# Output_Schematic.net
KiCad netlist of a schematic drawn in Altium Designer
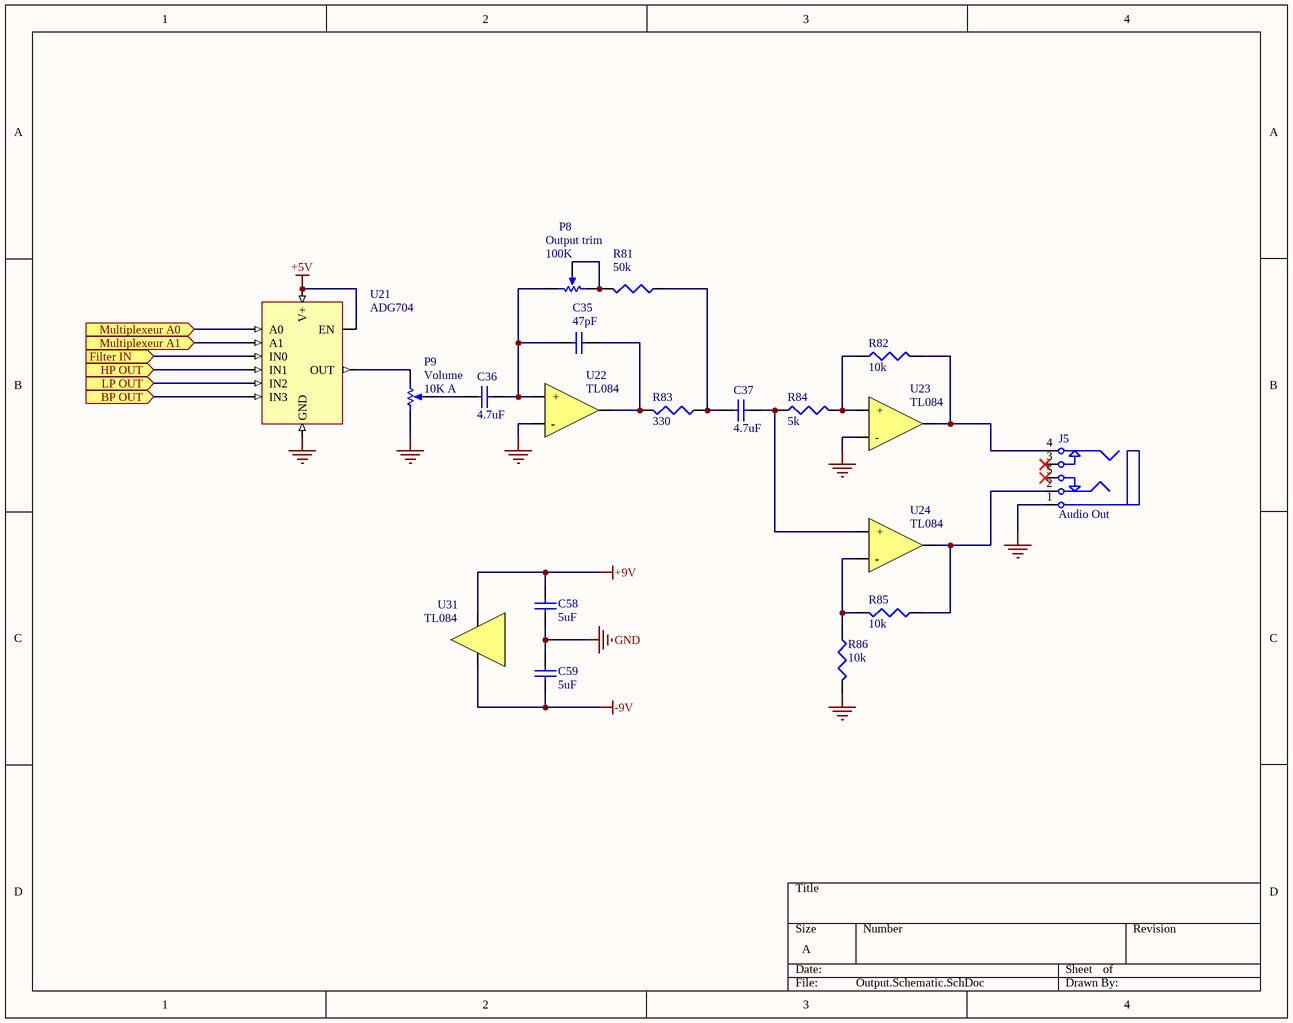
[diagram p0: Output.Schematic.SchDoc]

(export (version "E")
  (design (tool "Eeschema 10.0.6"))
  (components
    (comp (ref "C35")
      (value "47pF")
      (footprint "CAPC1608N")
      (description "Capacitor (Semiconductor SIM Model)")
      (fields (field (name "PUBLISHER") "Altium Limited"))
      (libsource (lib "Miscellaneous Devices") (part "Cap Semi"))
    )
    (comp (ref "C36")
      (value "4.7uF")
      (footprint "CAPC1608N")
      (description "Capacitor (Semiconductor SIM Model)")
      (fields (field (name "PUBLISHER") "Altium Limited"))
      (libsource (lib "Miscellaneous Devices") (part "Cap Semi"))
    )
    (comp (ref "C37")
      (value "4.7uF")
      (footprint "CAPC1608N")
      (description "Capacitor (Semiconductor SIM Model)")
      (fields (field (name "PUBLISHER") "Altium Limited"))
      (libsource (lib "Miscellaneous Devices") (part "Cap Semi"))
    )
    (comp (ref "C58")
      (value "5uF")
      (footprint "CAPC1608N")
      (description "Capacitor (Semiconductor SIM Model)")
      (fields (field (name "PUBLISHER") "Altium Limited"))
      (libsource (lib "Miscellaneous Devices") (part "Cap Semi"))
    )
    (comp (ref "C59")
      (value "5uF")
      (footprint "CAPC1608N")
      (description "Capacitor (Semiconductor SIM Model)")
      (fields (field (name "PUBLISHER") "Altium Limited"))
      (libsource (lib "Miscellaneous Devices") (part "Cap Semi"))
    )
    (comp (ref "J5")
      (value "Audio Out")
      (footprint "1503 09")
      (description "3-Conductor Jack with 2 break contacts (normals) and 2 auxiliary make contacts")
      (fields (field (name "PUBLISHER") "Altium Limited"))
      (libsource (lib "Miscellaneous Connectors") (part "Phonejack Stereo SW"))
    )
    (comp (ref "P8")
      (value "Output trim")
      (footprint "BOURNS Trim pot")
      (description "Potentiometer")
      (fields (field (name "ALTIUM_VALUE") "100K") (field (name "PUBLISHER") "Altium Limited"))
      (libsource (lib "Miscellaneous Devices") (part "RPot"))
    )
    (comp (ref "P9")
      (value "Volume")
      (footprint "ALPS Potentiometer")
      (description "Potentiometer")
      (fields (field (name "ALTIUM_VALUE") "10K A") (field (name "PUBLISHER") "Altium Limited"))
      (libsource (lib "Miscellaneous Devices") (part "RPot"))
    )
    (comp (ref "R81")
      (value "50k")
      (footprint "CAPC1608N")
      (description "Resistor")
      (fields (field (name "PUBLISHER") "Altium Limited"))
      (libsource (lib "Miscellaneous Devices") (part "Res3"))
    )
    (comp (ref "R82")
      (value "10k")
      (footprint "CAPC1608N")
      (description "Resistor")
      (fields (field (name "PUBLISHER") "Altium Limited"))
      (libsource (lib "Miscellaneous Devices") (part "Res3"))
    )
    (comp (ref "R83")
      (value "330")
      (footprint "CAPC1608N")
      (description "Resistor")
      (fields (field (name "PUBLISHER") "Altium Limited"))
      (libsource (lib "Miscellaneous Devices") (part "Res3"))
    )
    (comp (ref "R84")
      (value "5k")
      (footprint "CAPC1608N")
      (description "Resistor")
      (fields (field (name "PUBLISHER") "Altium Limited"))
      (libsource (lib "Miscellaneous Devices") (part "Res3"))
    )
    (comp (ref "R85")
      (value "10k")
      (footprint "CAPC1608N")
      (description "Resistor")
      (fields (field (name "PUBLISHER") "Altium Limited"))
      (libsource (lib "Miscellaneous Devices") (part "Res3"))
    )
    (comp (ref "R86")
      (value "10k")
      (footprint "CAPC1608N")
      (description "Resistor")
      (fields (field (name "PUBLISHER") "Altium Limited"))
      (libsource (lib "Miscellaneous Devices") (part "Res3"))
    )
    (comp (ref "U21")
      (value "ADG704")
      (footprint "ADG704")
      (libsource (lib "SynthyTwo.Components") (part "ADG704"))
    )
    (comp (ref "U22")
      (value "TL084")
      (footprint "TL084_3PADS")
      (libsource (lib "SynthyTwo.Components") (part "TL084"))
    )
    (comp (ref "U23")
      (value "TL084")
      (footprint "TL084_3PADS")
      (libsource (lib "SynthyTwo.Components") (part "TL084"))
    )
    (comp (ref "U24")
      (value "TL084")
      (footprint "TL084_3PADS")
      (libsource (lib "SynthyTwo.Components") (part "TL084"))
    )
    (comp (ref "U31")
      (value "TL084")
      (footprint "TL084_ALIM")
      (libsource (lib "SynthyTwo.Components") (part "TL_CLEAN"))
    )
  )
  (nets
    (net (code "1") (name "+5V") (class "Default")
      (node (ref "U21") (pin "5") (pinfunction "EN_5") (pintype "passive"))
      (node (ref "U21") (pin "6") (pinfunction "V+_6") (pintype "input"))
    )
    (net (code "2") (name "+9V") (class "Default")
      (node (ref "C58") (pin "1") (pinfunction "1_1") (pintype "passive"))
      (node (ref "U31") (pin "2") (pinfunction "VCC-_2") (pintype "passive"))
    )
    (net (code "3") (name "-9V") (class "Default")
      (node (ref "C59") (pin "2") (pinfunction "2_2") (pintype "passive"))
      (node (ref "U31") (pin "1") (pinfunction "VCC+_1") (pintype "passive"))
    )
    (net (code "4") (name "/BP OUT") (class "Default")
      (node (ref "U21") (pin "7") (pinfunction "IN3_7") (pintype "input"))
    )
    (net (code "5") (name "/Filter IN") (class "Default")
      (node (ref "U21") (pin "2") (pinfunction "IN0_2") (pintype "input"))
    )
    (net (code "6") (name "/HP OUT") (class "Default")
      (node (ref "U21") (pin "9") (pinfunction "IN1_9") (pintype "input"))
    )
    (net (code "7") (name "/LP OUT") (class "Default")
      (node (ref "U21") (pin "4") (pinfunction "IN2_4") (pintype "input"))
    )
    (net (code "8") (name "/Multiplexeur A0") (class "Default")
      (node (ref "U21") (pin "1") (pinfunction "A0_1") (pintype "input"))
    )
    (net (code "9") (name "/Multiplexeur A1") (class "Default")
      (node (ref "U21") (pin "10") (pinfunction "A1_10") (pintype "input"))
    )
    (net (code "10") (name "GND") (class "Default")
      (node (ref "C58") (pin "2") (pinfunction "2_2") (pintype "passive"))
      (node (ref "C59") (pin "1") (pinfunction "1_1") (pintype "passive"))
      (node (ref "J5") (pin "1") (pinfunction "1_1") (pintype "passive"))
      (node (ref "P9") (pin "1") (pinfunction "TOP_1") (pintype "passive"))
      (node (ref "R86") (pin "2") (pinfunction "2_2") (pintype "passive"))
      (node (ref "U21") (pin "3") (pinfunction "GND_3") (pintype "input"))
      (node (ref "U22") (pin "2") (pinfunction "-_2") (pintype "passive"))
      (node (ref "U23") (pin "2") (pinfunction "-_2") (pintype "passive"))
    )
    (net (code "11") (name "Net-(C37-Pad1)") (class "Default")
      (node (ref "C37") (pin "1") (pinfunction "1_1") (pintype "passive"))
      (node (ref "R81") (pin "1") (pinfunction "1_1") (pintype "passive"))
      (node (ref "R83") (pin "1") (pinfunction "1_1") (pintype "passive"))
    )
    (net (code "12") (name "Net-(P8-BOT)") (class "Default")
      (node (ref "P8") (pin "2") (pinfunction "BOT_2") (pintype "passive"))
      (node (ref "P8") (pin "3") (pinfunction "TAP_3") (pintype "passive"))
      (node (ref "R81") (pin "2") (pinfunction "2_2") (pintype "passive"))
    )
    (net (code "13") (name "Net-(P8-TOP)") (class "Default")
      (node (ref "C35") (pin "1") (pinfunction "1_1") (pintype "passive"))
      (node (ref "C36") (pin "2") (pinfunction "2_2") (pintype "passive"))
      (node (ref "P8") (pin "1") (pinfunction "TOP_1") (pintype "passive"))
      (node (ref "U22") (pin "3") (pinfunction "+_3") (pintype "passive"))
    )
    (net (code "14") (name "Net-(P9-BOT)") (class "Default")
      (node (ref "P9") (pin "2") (pinfunction "BOT_2") (pintype "passive"))
      (node (ref "U21") (pin "8") (pinfunction "OUT_8") (pintype "output"))
    )
    (net (code "15") (name "Net-(P9-TAP)") (class "Default")
      (node (ref "C36") (pin "1") (pinfunction "1_1") (pintype "passive"))
      (node (ref "P9") (pin "3") (pinfunction "TAP_3") (pintype "passive"))
    )
    (net (code "16") (name "Net-(U22-OUT)") (class "Default")
      (node (ref "C35") (pin "2") (pinfunction "2_2") (pintype "passive"))
      (node (ref "R83") (pin "2") (pinfunction "2_2") (pintype "passive"))
      (node (ref "U22") (pin "1") (pinfunction "OUT_1") (pintype "passive"))
    )
    (net (code "17") (name "Net-(U23-+)") (class "Default")
      (node (ref "R82") (pin "1") (pinfunction "1_1") (pintype "passive"))
      (node (ref "R84") (pin "2") (pinfunction "2_2") (pintype "passive"))
      (node (ref "U23") (pin "3") (pinfunction "+_3") (pintype "passive"))
    )
    (net (code "18") (name "Net-(U23-OUT)") (class "Default")
      (node (ref "J5") (pin "4") (pinfunction "4_4") (pintype "passive"))
      (node (ref "R82") (pin "2") (pinfunction "2_2") (pintype "passive"))
      (node (ref "U23") (pin "1") (pinfunction "OUT_1") (pintype "passive"))
    )
    (net (code "19") (name "Net-(U24-+)") (class "Default")
      (node (ref "C37") (pin "2") (pinfunction "2_2") (pintype "passive"))
      (node (ref "R84") (pin "1") (pinfunction "1_1") (pintype "passive"))
      (node (ref "U24") (pin "3") (pinfunction "+_3") (pintype "passive"))
    )
    (net (code "20") (name "Net-(U24--)") (class "Default")
      (node (ref "R85") (pin "2") (pinfunction "2_2") (pintype "passive"))
      (node (ref "R86") (pin "1") (pinfunction "1_1") (pintype "passive"))
      (node (ref "U24") (pin "2") (pinfunction "-_2") (pintype "passive"))
    )
    (net (code "21") (name "Net-(U24-OUT)") (class "Default")
      (node (ref "J5") (pin "2") (pinfunction "2_2") (pintype "passive"))
      (node (ref "R85") (pin "1") (pinfunction "1_1") (pintype "passive"))
      (node (ref "U24") (pin "1") (pinfunction "OUT_1") (pintype "passive"))
    )
    (net (code "22") (name "unconnected-(J5-Pad3)") (class "Default")
      (node (ref "J5") (pin "3") (pinfunction "3_3") (pintype "passive+no_connect"))
    )
    (net (code "23") (name "unconnected-(J5-Pad5)") (class "Default")
      (node (ref "J5") (pin "5") (pinfunction "5_5") (pintype "passive+no_connect"))
    )
  )
)
